# Sheet1.net
KiCad netlist of a schematic drawn in Altium Designer
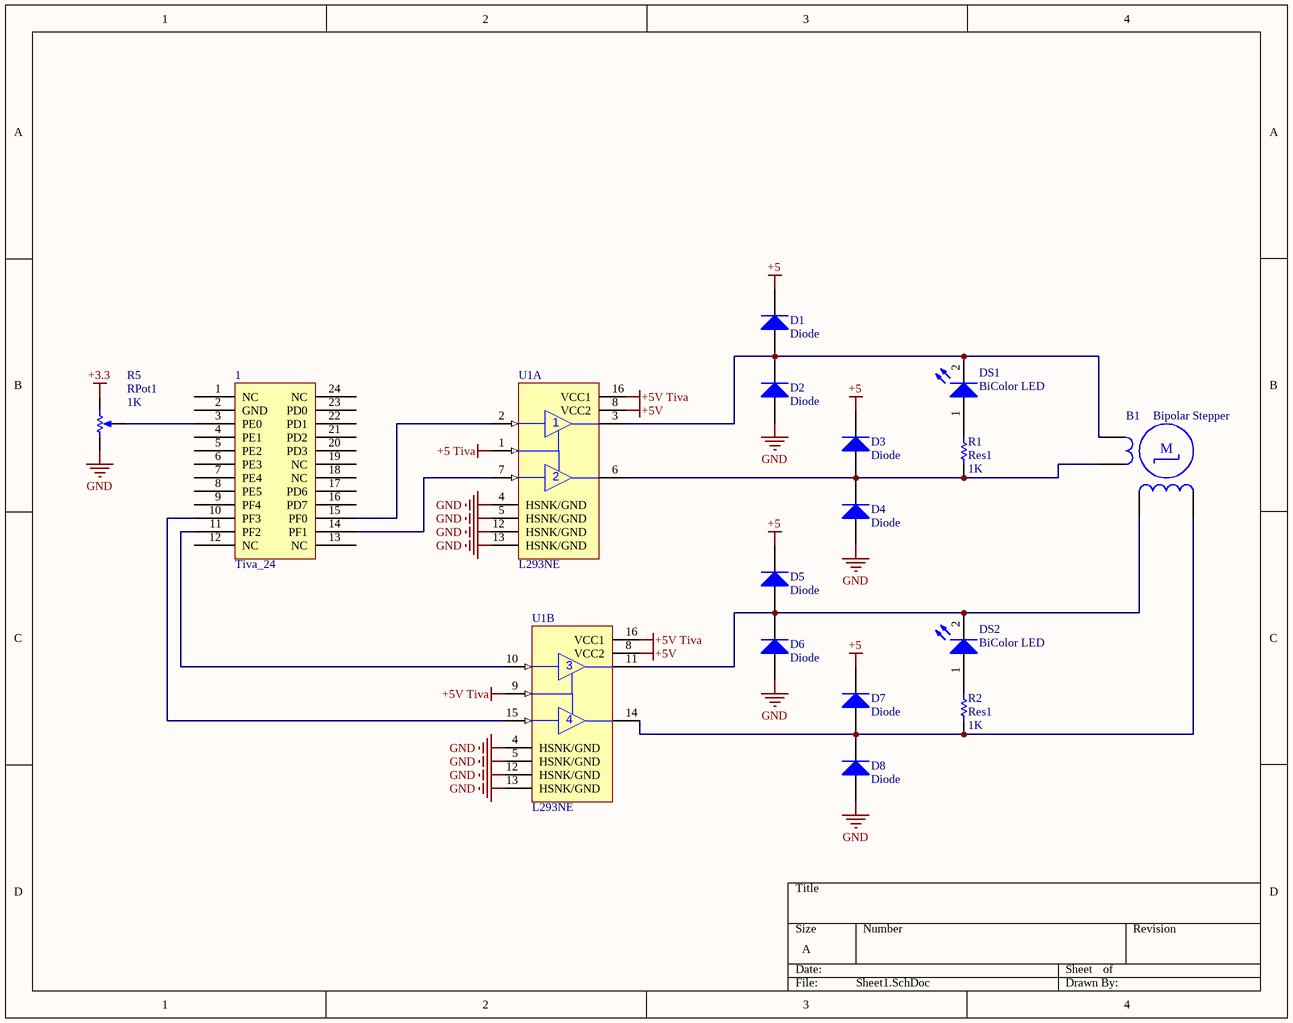
[diagram p0: Sheet1.SchDoc]

(export (version "E")
  (design (tool "Eeschema 10.0.6"))
  (components
    (comp (ref "1")
      (value "Tiva_24")
      (description "Tiva Protection 24 Pin Connector")
      (libsource (lib "ME218_BaseLib") (part "Tiva_24"))
    )
    (comp (ref "B1")
      (value "Bipolar Stepper")
      (footprint "DIP-6")
      (description "Motor Stepper")
      (fields (field (name "MANUFACTURER") "Generic Components"))
      (libsource (lib "ME218_BaseLib") (part "Motor Step 4Wire"))
    )
    (comp (ref "D1")
      (value "Diode")
      (footprint "DSO-C2/X3.3")
      (description "Default Diode")
      (fields
        (field (name "MANUFACTURER") "Generic Components")
        (field (name "PUBLISHER") "Altium Hobart Technology Centre")
      )
      (libsource (lib "ME218_BaseLib") (part "Diode"))
    )
    (comp (ref "D2")
      (value "Diode")
      (footprint "DSO-C2/X3.3")
      (description "Default Diode")
      (fields
        (field (name "MANUFACTURER") "Generic Components")
        (field (name "PUBLISHER") "Altium Hobart Technology Centre")
      )
      (libsource (lib "ME218_BaseLib") (part "Diode"))
    )
    (comp (ref "D3")
      (value "Diode")
      (footprint "DSO-C2/X3.3")
      (description "Default Diode")
      (fields
        (field (name "MANUFACTURER") "Generic Components")
        (field (name "PUBLISHER") "Altium Hobart Technology Centre")
      )
      (libsource (lib "ME218_BaseLib") (part "Diode"))
    )
    (comp (ref "D4")
      (value "Diode")
      (footprint "DSO-C2/X3.3")
      (description "Default Diode")
      (fields
        (field (name "MANUFACTURER") "Generic Components")
        (field (name "PUBLISHER") "Altium Hobart Technology Centre")
      )
      (libsource (lib "ME218_BaseLib") (part "Diode"))
    )
    (comp (ref "D5")
      (value "Diode")
      (footprint "DSO-C2/X3.3")
      (description "Default Diode")
      (fields
        (field (name "MANUFACTURER") "Generic Components")
        (field (name "PUBLISHER") "Altium Hobart Technology Centre")
      )
      (libsource (lib "ME218_BaseLib") (part "Diode"))
    )
    (comp (ref "D6")
      (value "Diode")
      (footprint "DSO-C2/X3.3")
      (description "Default Diode")
      (fields
        (field (name "MANUFACTURER") "Generic Components")
        (field (name "PUBLISHER") "Altium Hobart Technology Centre")
      )
      (libsource (lib "ME218_BaseLib") (part "Diode"))
    )
    (comp (ref "D7")
      (value "Diode")
      (footprint "DSO-C2/X3.3")
      (description "Default Diode")
      (fields
        (field (name "MANUFACTURER") "Generic Components")
        (field (name "PUBLISHER") "Altium Hobart Technology Centre")
      )
      (libsource (lib "ME218_BaseLib") (part "Diode"))
    )
    (comp (ref "D8")
      (value "Diode")
      (footprint "DSO-C2/X3.3")
      (description "Default Diode")
      (fields
        (field (name "MANUFACTURER") "Generic Components")
        (field (name "PUBLISHER") "Altium Hobart Technology Centre")
      )
      (libsource (lib "ME218_BaseLib") (part "Diode"))
    )
    (comp (ref "DS1")
      (value "BiColor LED")
      (footprint "LED-0")
      (description "Typical INFRARED GaAs LED")
      (fields
        (field (name "MANUFACTURER") "Generic Components")
        (field (name "PUBLISHER") "Altium Hobart Technology Centre")
      )
      (libsource (lib "ME218_BaseLib") (part "LED0"))
    )
    (comp (ref "DS2")
      (value "BiColor LED")
      (footprint "LED-0")
      (description "Typical INFRARED GaAs LED")
      (fields
        (field (name "MANUFACTURER") "Generic Components")
        (field (name "PUBLISHER") "Altium Hobart Technology Centre")
      )
      (libsource (lib "ME218_BaseLib") (part "LED0"))
    )
    (comp (ref "R1")
      (value "Res1")
      (footprint "AXIAL-0.3")
      (description "Resistor")
      (fields
        (field (name "MANUFACTURER") "Generic Components")
        (field (name "ALTIUM_VALUE") "1K")
        (field (name "PUBLISHER") "Altium Hobart Technology Centre")
      )
      (libsource (lib "ME218_BaseLib") (part "Res1"))
    )
    (comp (ref "R2")
      (value "Res1")
      (footprint "AXIAL-0.3")
      (description "Resistor")
      (fields
        (field (name "MANUFACTURER") "Generic Components")
        (field (name "ALTIUM_VALUE") "1K")
        (field (name "PUBLISHER") "Altium Hobart Technology Centre")
      )
      (libsource (lib "ME218_BaseLib") (part "Res1"))
    )
    (comp (ref "R5")
      (value "RPot1")
      (footprint "VR5")
      (description "Potentiometer")
      (fields
        (field (name "MANUFACTURER") "Generic Components")
        (field (name "ALTIUM_VALUE") "1K")
        (field (name "PUBLISHER") "Altium Hobart Technology Centre")
      )
      (libsource (lib "ME218_BaseLib") (part "RPot1"))
    )
    (comp (ref "U1")
      (value "L293NE")
      (footprint "DIP-16/X1.5")
      (description "Quadruple Half-H Driver")
      (fields
        (field (name "MANUFACTURER") "Texas Instruments")
        (field (name "PUBLISHER") "Altium Hobart Technology Centre")
      )
      (libsource (lib "ME218_BaseLib") (part "L293NE"))
    )
  )
  (nets
    (net (code "1") (name "+3.3") (class "Default")
      (node (ref "R5") (pin "2") (pinfunction "BOT_2") (pintype "passive"))
    )
    (net (code "2") (name "+5") (class "Default")
      (node (ref "D1") (pin "2") (pinfunction "K_2") (pintype "passive"))
      (node (ref "D3") (pin "2") (pinfunction "K_2") (pintype "passive"))
      (node (ref "D5") (pin "2") (pinfunction "K_2") (pintype "passive"))
      (node (ref "D7") (pin "2") (pinfunction "K_2") (pintype "passive"))
    )
    (net (code "3") (name "+5 Tiva") (class "Default")
      (node (ref "U1") (pin "1") (pinfunction "1,2EN_1") (pintype "input"))
    )
    (net (code "4") (name "+5V") (class "Default")
      (node (ref "U1") (pin "8") (pinfunction "VCC2_8") (pintype "power_in"))
    )
    (net (code "5") (name "+5V Tiva") (class "Default")
      (node (ref "U1") (pin "16") (pinfunction "VCC1_16") (pintype "power_in"))
      (node (ref "U1") (pin "9") (pinfunction "3,4EN_9") (pintype "input"))
    )
    (net (code "6") (name "GND") (class "Default")
      (node (ref "D2") (pin "1") (pinfunction "A_1") (pintype "passive"))
      (node (ref "D4") (pin "1") (pinfunction "A_1") (pintype "passive"))
      (node (ref "D6") (pin "1") (pinfunction "A_1") (pintype "passive"))
      (node (ref "D8") (pin "1") (pinfunction "A_1") (pintype "passive"))
      (node (ref "R5") (pin "1") (pinfunction "TOP_1") (pintype "passive"))
      (node (ref "U1") (pin "12") (pinfunction "HSNK/GND_12") (pintype "power_in"))
      (node (ref "U1") (pin "13") (pinfunction "HSNK/GND_13") (pintype "power_in"))
      (node (ref "U1") (pin "4") (pinfunction "HSNK/GND_4") (pintype "power_in"))
      (node (ref "U1") (pin "5") (pinfunction "HSNK/GND_5") (pintype "power_in"))
    )
    (net (code "7") (name "Net-(1-PE0)") (class "Default")
      (node (ref "1") (pin "3") (pinfunction "PE0_3") (pintype "passive"))
      (node (ref "R5") (pin "3") (pinfunction "TAP_3") (pintype "passive"))
    )
    (net (code "8") (name "Net-(1-PF0)") (class "Default")
      (node (ref "1") (pin "15") (pinfunction "PF0_15") (pintype "passive"))
      (node (ref "U1") (pin "2") (pinfunction "1A_2") (pintype "input"))
    )
    (net (code "9") (name "Net-(1-PF1)") (class "Default")
      (node (ref "1") (pin "14") (pinfunction "PF1_14") (pintype "passive"))
      (node (ref "U1") (pin "7") (pinfunction "2A_7") (pintype "input"))
    )
    (net (code "10") (name "Net-(1-PF2)") (class "Default")
      (node (ref "1") (pin "11") (pinfunction "PF2_11") (pintype "passive"))
      (node (ref "U1") (pin "10") (pinfunction "3A_10") (pintype "input"))
    )
    (net (code "11") (name "Net-(1-PF3)") (class "Default")
      (node (ref "1") (pin "10") (pinfunction "PF3_10") (pintype "passive"))
      (node (ref "U1") (pin "15") (pinfunction "4A_15") (pintype "input"))
    )
    (net (code "12") (name "Net-(D1-A)") (class "Default")
      (node (ref "B1") (pin "1") (pinfunction "1_1") (pintype "passive"))
      (node (ref "D1") (pin "1") (pinfunction "A_1") (pintype "passive"))
      (node (ref "D2") (pin "2") (pinfunction "K_2") (pintype "passive"))
      (node (ref "DS1") (pin "2") (pinfunction "K_2") (pintype "passive"))
      (node (ref "U1") (pin "3") (pinfunction "1Y_3") (pintype "tri_state"))
    )
    (net (code "13") (name "Net-(D3-A)") (class "Default")
      (node (ref "B1") (pin "3") (pinfunction "3_3") (pintype "passive"))
      (node (ref "D3") (pin "1") (pinfunction "A_1") (pintype "passive"))
      (node (ref "D4") (pin "2") (pinfunction "K_2") (pintype "passive"))
      (node (ref "R1") (pin "1") (pinfunction "1_1") (pintype "passive"))
      (node (ref "U1") (pin "6") (pinfunction "2Y_6") (pintype "tri_state"))
    )
    (net (code "14") (name "Net-(D5-A)") (class "Default")
      (node (ref "B1") (pin "4") (pinfunction "4_4") (pintype "passive"))
      (node (ref "D5") (pin "1") (pinfunction "A_1") (pintype "passive"))
      (node (ref "D6") (pin "2") (pinfunction "K_2") (pintype "passive"))
      (node (ref "DS2") (pin "2") (pinfunction "K_2") (pintype "passive"))
      (node (ref "U1") (pin "11") (pinfunction "3Y_11") (pintype "tri_state"))
    )
    (net (code "15") (name "Net-(D7-A)") (class "Default")
      (node (ref "B1") (pin "6") (pinfunction "6_6") (pintype "passive"))
      (node (ref "D7") (pin "1") (pinfunction "A_1") (pintype "passive"))
      (node (ref "D8") (pin "2") (pinfunction "K_2") (pintype "passive"))
      (node (ref "R2") (pin "1") (pinfunction "1_1") (pintype "passive"))
      (node (ref "U1") (pin "14") (pinfunction "4Y_14") (pintype "tri_state"))
    )
    (net (code "16") (name "Net-(DS1-A)") (class "Default")
      (node (ref "DS1") (pin "1") (pinfunction "A_1") (pintype "passive"))
      (node (ref "R1") (pin "2") (pinfunction "2_2") (pintype "passive"))
    )
    (net (code "17") (name "Net-(DS2-A)") (class "Default")
      (node (ref "DS2") (pin "1") (pinfunction "A_1") (pintype "passive"))
      (node (ref "R2") (pin "2") (pinfunction "2_2") (pintype "passive"))
    )
    (net (code "18") (name "unconnected-(1-GND-Pad2)") (class "Default")
      (node (ref "1") (pin "2") (pinfunction "GND_2") (pintype "passive"))
    )
    (net (code "19") (name "unconnected-(1-NC-Pad1)") (class "Default")
      (node (ref "1") (pin "1") (pinfunction "NC_1") (pintype "passive"))
    )
    (net (code "20") (name "unconnected-(1-NC-Pad12)") (class "Default")
      (node (ref "1") (pin "12") (pinfunction "NC_12") (pintype "passive"))
    )
    (net (code "21") (name "unconnected-(1-NC-Pad13)") (class "Default")
      (node (ref "1") (pin "13") (pinfunction "NC_13") (pintype "passive"))
    )
    (net (code "22") (name "unconnected-(1-NC-Pad18)") (class "Default")
      (node (ref "1") (pin "18") (pinfunction "NC_18") (pintype "passive"))
    )
    (net (code "23") (name "unconnected-(1-NC-Pad19)") (class "Default")
      (node (ref "1") (pin "19") (pinfunction "NC_19") (pintype "passive"))
    )
    (net (code "24") (name "unconnected-(1-NC-Pad24)") (class "Default")
      (node (ref "1") (pin "24") (pinfunction "NC_24") (pintype "passive"))
    )
    (net (code "25") (name "unconnected-(1-PD0-Pad23)") (class "Default")
      (node (ref "1") (pin "23") (pinfunction "PD0_23") (pintype "passive"))
    )
    (net (code "26") (name "unconnected-(1-PD1-Pad22)") (class "Default")
      (node (ref "1") (pin "22") (pinfunction "PD1_22") (pintype "passive"))
    )
    (net (code "27") (name "unconnected-(1-PD2-Pad21)") (class "Default")
      (node (ref "1") (pin "21") (pinfunction "PD2_21") (pintype "passive"))
    )
    (net (code "28") (name "unconnected-(1-PD3-Pad20)") (class "Default")
      (node (ref "1") (pin "20") (pinfunction "PD3_20") (pintype "passive"))
    )
    (net (code "29") (name "unconnected-(1-PD6-Pad17)") (class "Default")
      (node (ref "1") (pin "17") (pinfunction "PD6_17") (pintype "passive"))
    )
    (net (code "30") (name "unconnected-(1-PD7-Pad16)") (class "Default")
      (node (ref "1") (pin "16") (pinfunction "PD7_16") (pintype "passive"))
    )
    (net (code "31") (name "unconnected-(1-PE1-Pad4)") (class "Default")
      (node (ref "1") (pin "4") (pinfunction "PE1_4") (pintype "passive"))
    )
    (net (code "32") (name "unconnected-(1-PE2-Pad5)") (class "Default")
      (node (ref "1") (pin "5") (pinfunction "PE2_5") (pintype "passive"))
    )
    (net (code "33") (name "unconnected-(1-PE3-Pad6)") (class "Default")
      (node (ref "1") (pin "6") (pinfunction "PE3_6") (pintype "passive"))
    )
    (net (code "34") (name "unconnected-(1-PE4-Pad7)") (class "Default")
      (node (ref "1") (pin "7") (pinfunction "PE4_7") (pintype "passive"))
    )
    (net (code "35") (name "unconnected-(1-PE5-Pad8)") (class "Default")
      (node (ref "1") (pin "8") (pinfunction "PE5_8") (pintype "passive"))
    )
    (net (code "36") (name "unconnected-(1-PF4-Pad9)") (class "Default")
      (node (ref "1") (pin "9") (pinfunction "PF4_9") (pintype "passive"))
    )
  )
)
